# nixie_tubes.net
KiCad netlist of a schematic drawn in EAGLE
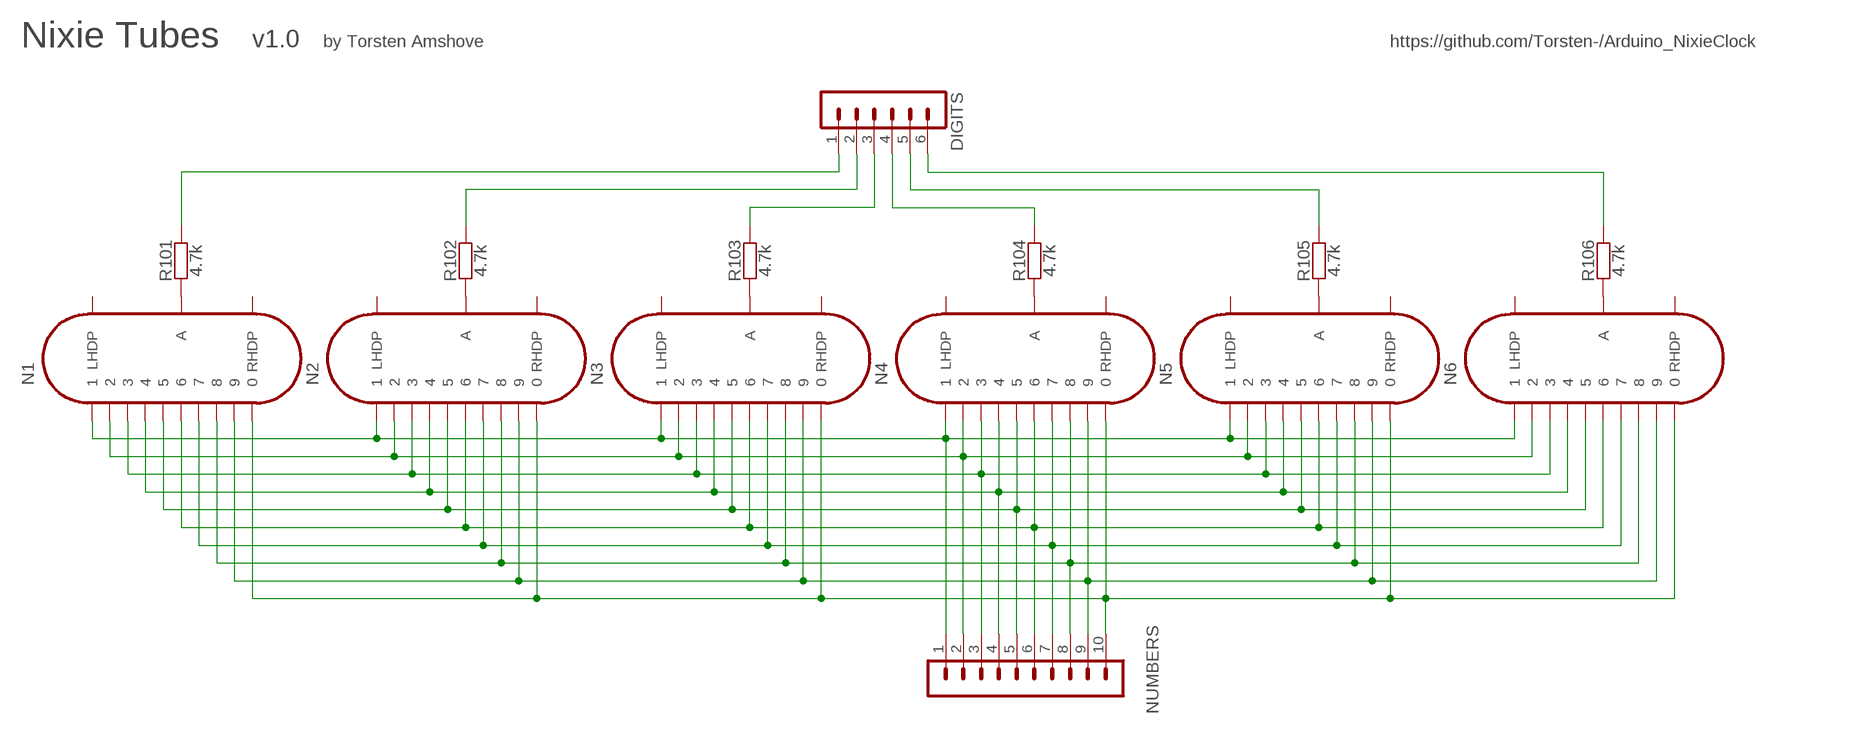
[diagram p0: schematic, sheet 1]

(export (version "E")
  (design (tool "Eeschema 10.0.6"))
  (components
    (comp (ref "DIGITS")
      (value "MA06-1")
      (footprint "eagle-import:MA06-1")
      (libsource (lib "eagle-import") (part "MA06-1"))
    )
    (comp (ref "N1")
      (value "IN-14")
      (footprint "eagle-import:IN-14")
      (libsource (lib "eagle-import") (part "IN-14"))
    )
    (comp (ref "N2")
      (value "IN-14")
      (footprint "eagle-import:IN-14")
      (libsource (lib "eagle-import") (part "IN-14"))
    )
    (comp (ref "N3")
      (value "IN-14")
      (footprint "eagle-import:IN-14")
      (libsource (lib "eagle-import") (part "IN-14"))
    )
    (comp (ref "N4")
      (value "IN-14")
      (footprint "eagle-import:IN-14")
      (libsource (lib "eagle-import") (part "IN-14"))
    )
    (comp (ref "N5")
      (value "IN-14")
      (footprint "eagle-import:IN-14")
      (libsource (lib "eagle-import") (part "IN-14"))
    )
    (comp (ref "N6")
      (value "IN-14")
      (footprint "eagle-import:IN-14")
      (libsource (lib "eagle-import") (part "IN-14"))
    )
    (comp (ref "NUMBERS")
      (value "MA10-1")
      (footprint "eagle-import:MA10-1")
      (libsource (lib "eagle-import") (part "MA10-1"))
    )
    (comp (ref "R101")
      (value "4.7k")
      (footprint "eagle-import:R0207_10")
      (libsource (lib "eagle-import") (part "RESISTOR-10"))
    )
    (comp (ref "R102")
      (value "4.7k")
      (footprint "eagle-import:R0207_10")
      (libsource (lib "eagle-import") (part "RESISTOR-10"))
    )
    (comp (ref "R103")
      (value "4.7k")
      (footprint "eagle-import:R0207_10")
      (libsource (lib "eagle-import") (part "RESISTOR-10"))
    )
    (comp (ref "R104")
      (value "4.7k")
      (footprint "eagle-import:R0207_10")
      (libsource (lib "eagle-import") (part "RESISTOR-10"))
    )
    (comp (ref "R105")
      (value "4.7k")
      (footprint "eagle-import:R0207_10")
      (libsource (lib "eagle-import") (part "RESISTOR-10"))
    )
    (comp (ref "R106")
      (value "4.7k")
      (footprint "eagle-import:R0207_10")
      (libsource (lib "eagle-import") (part "RESISTOR-10"))
    )
  )
  (nets
    (net (code "1") (name "Net-(DIGITS-Pad1)") (class "Default")
      (node (ref "DIGITS") (pin "1") (pinfunction "1_1") (pintype "passive"))
      (node (ref "R101") (pin "2") (pinfunction "2_2") (pintype "passive"))
    )
    (net (code "2") (name "Net-(DIGITS-Pad2)") (class "Default")
      (node (ref "DIGITS") (pin "2") (pinfunction "2_2") (pintype "passive"))
      (node (ref "R102") (pin "2") (pinfunction "2_2") (pintype "passive"))
    )
    (net (code "3") (name "Net-(DIGITS-Pad3)") (class "Default")
      (node (ref "DIGITS") (pin "3") (pinfunction "3_3") (pintype "passive"))
      (node (ref "R103") (pin "2") (pinfunction "2_2") (pintype "passive"))
    )
    (net (code "4") (name "Net-(DIGITS-Pad4)") (class "Default")
      (node (ref "DIGITS") (pin "4") (pinfunction "4_4") (pintype "passive"))
      (node (ref "R104") (pin "2") (pinfunction "2_2") (pintype "passive"))
    )
    (net (code "5") (name "Net-(DIGITS-Pad5)") (class "Default")
      (node (ref "DIGITS") (pin "5") (pinfunction "5_5") (pintype "passive"))
      (node (ref "R105") (pin "2") (pinfunction "2_2") (pintype "passive"))
    )
    (net (code "6") (name "Net-(DIGITS-Pad6)") (class "Default")
      (node (ref "DIGITS") (pin "6") (pinfunction "6_6") (pintype "passive"))
      (node (ref "R106") (pin "2") (pinfunction "2_2") (pintype "passive"))
    )
    (net (code "7") (name "Net-(N1-Pad0)") (class "Default")
      (node (ref "N1") (pin "0") (pinfunction "0_0") (pintype "bidirectional"))
      (node (ref "N2") (pin "0") (pinfunction "0_0") (pintype "bidirectional"))
      (node (ref "N3") (pin "0") (pinfunction "0_0") (pintype "bidirectional"))
      (node (ref "N4") (pin "0") (pinfunction "0_0") (pintype "bidirectional"))
      (node (ref "N5") (pin "0") (pinfunction "0_0") (pintype "bidirectional"))
      (node (ref "N6") (pin "0") (pinfunction "0_0") (pintype "bidirectional"))
      (node (ref "NUMBERS") (pin "10") (pinfunction "10_10") (pintype "passive"))
    )
    (net (code "8") (name "Net-(N1-Pad1)") (class "Default")
      (node (ref "N1") (pin "1") (pinfunction "1_1") (pintype "bidirectional"))
      (node (ref "N2") (pin "1") (pinfunction "1_1") (pintype "bidirectional"))
      (node (ref "N3") (pin "1") (pinfunction "1_1") (pintype "bidirectional"))
      (node (ref "N4") (pin "1") (pinfunction "1_1") (pintype "bidirectional"))
      (node (ref "N5") (pin "1") (pinfunction "1_1") (pintype "bidirectional"))
      (node (ref "N6") (pin "1") (pinfunction "1_1") (pintype "bidirectional"))
      (node (ref "NUMBERS") (pin "1") (pinfunction "1_1") (pintype "passive"))
    )
    (net (code "9") (name "Net-(N1-Pad2)") (class "Default")
      (node (ref "N1") (pin "2") (pinfunction "2_2") (pintype "bidirectional"))
      (node (ref "N2") (pin "2") (pinfunction "2_2") (pintype "bidirectional"))
      (node (ref "N3") (pin "2") (pinfunction "2_2") (pintype "bidirectional"))
      (node (ref "N4") (pin "2") (pinfunction "2_2") (pintype "bidirectional"))
      (node (ref "N5") (pin "2") (pinfunction "2_2") (pintype "bidirectional"))
      (node (ref "N6") (pin "2") (pinfunction "2_2") (pintype "bidirectional"))
      (node (ref "NUMBERS") (pin "2") (pinfunction "2_2") (pintype "passive"))
    )
    (net (code "10") (name "Net-(N1-Pad3)") (class "Default")
      (node (ref "N1") (pin "3") (pinfunction "3_3") (pintype "bidirectional"))
      (node (ref "N2") (pin "3") (pinfunction "3_3") (pintype "bidirectional"))
      (node (ref "N3") (pin "3") (pinfunction "3_3") (pintype "bidirectional"))
      (node (ref "N4") (pin "3") (pinfunction "3_3") (pintype "bidirectional"))
      (node (ref "N5") (pin "3") (pinfunction "3_3") (pintype "bidirectional"))
      (node (ref "N6") (pin "3") (pinfunction "3_3") (pintype "bidirectional"))
      (node (ref "NUMBERS") (pin "3") (pinfunction "3_3") (pintype "passive"))
    )
    (net (code "11") (name "Net-(N1-Pad4)") (class "Default")
      (node (ref "N1") (pin "4") (pinfunction "4_4") (pintype "bidirectional"))
      (node (ref "N2") (pin "4") (pinfunction "4_4") (pintype "bidirectional"))
      (node (ref "N3") (pin "4") (pinfunction "4_4") (pintype "bidirectional"))
      (node (ref "N4") (pin "4") (pinfunction "4_4") (pintype "bidirectional"))
      (node (ref "N5") (pin "4") (pinfunction "4_4") (pintype "bidirectional"))
      (node (ref "N6") (pin "4") (pinfunction "4_4") (pintype "bidirectional"))
      (node (ref "NUMBERS") (pin "4") (pinfunction "4_4") (pintype "passive"))
    )
    (net (code "12") (name "Net-(N1-Pad5)") (class "Default")
      (node (ref "N1") (pin "5") (pinfunction "5_5") (pintype "bidirectional"))
      (node (ref "N2") (pin "5") (pinfunction "5_5") (pintype "bidirectional"))
      (node (ref "N3") (pin "5") (pinfunction "5_5") (pintype "bidirectional"))
      (node (ref "N4") (pin "5") (pinfunction "5_5") (pintype "bidirectional"))
      (node (ref "N5") (pin "5") (pinfunction "5_5") (pintype "bidirectional"))
      (node (ref "N6") (pin "5") (pinfunction "5_5") (pintype "bidirectional"))
      (node (ref "NUMBERS") (pin "5") (pinfunction "5_5") (pintype "passive"))
    )
    (net (code "13") (name "Net-(N1-Pad6)") (class "Default")
      (node (ref "N1") (pin "6") (pinfunction "6_6") (pintype "bidirectional"))
      (node (ref "N2") (pin "6") (pinfunction "6_6") (pintype "bidirectional"))
      (node (ref "N3") (pin "6") (pinfunction "6_6") (pintype "bidirectional"))
      (node (ref "N4") (pin "6") (pinfunction "6_6") (pintype "bidirectional"))
      (node (ref "N5") (pin "6") (pinfunction "6_6") (pintype "bidirectional"))
      (node (ref "N6") (pin "6") (pinfunction "6_6") (pintype "bidirectional"))
      (node (ref "NUMBERS") (pin "6") (pinfunction "6_6") (pintype "passive"))
    )
    (net (code "14") (name "Net-(N1-Pad7)") (class "Default")
      (node (ref "N1") (pin "7") (pinfunction "7_7") (pintype "bidirectional"))
      (node (ref "N2") (pin "7") (pinfunction "7_7") (pintype "bidirectional"))
      (node (ref "N3") (pin "7") (pinfunction "7_7") (pintype "bidirectional"))
      (node (ref "N4") (pin "7") (pinfunction "7_7") (pintype "bidirectional"))
      (node (ref "N5") (pin "7") (pinfunction "7_7") (pintype "bidirectional"))
      (node (ref "N6") (pin "7") (pinfunction "7_7") (pintype "bidirectional"))
      (node (ref "NUMBERS") (pin "7") (pinfunction "7_7") (pintype "passive"))
    )
    (net (code "15") (name "Net-(N1-Pad8)") (class "Default")
      (node (ref "N1") (pin "8") (pinfunction "8_8") (pintype "bidirectional"))
      (node (ref "N2") (pin "8") (pinfunction "8_8") (pintype "bidirectional"))
      (node (ref "N3") (pin "8") (pinfunction "8_8") (pintype "bidirectional"))
      (node (ref "N4") (pin "8") (pinfunction "8_8") (pintype "bidirectional"))
      (node (ref "N5") (pin "8") (pinfunction "8_8") (pintype "bidirectional"))
      (node (ref "N6") (pin "8") (pinfunction "8_8") (pintype "bidirectional"))
      (node (ref "NUMBERS") (pin "8") (pinfunction "8_8") (pintype "passive"))
    )
    (net (code "16") (name "Net-(N1-Pad9)") (class "Default")
      (node (ref "N1") (pin "9") (pinfunction "9_9") (pintype "bidirectional"))
      (node (ref "N2") (pin "9") (pinfunction "9_9") (pintype "bidirectional"))
      (node (ref "N3") (pin "9") (pinfunction "9_9") (pintype "bidirectional"))
      (node (ref "N4") (pin "9") (pinfunction "9_9") (pintype "bidirectional"))
      (node (ref "N5") (pin "9") (pinfunction "9_9") (pintype "bidirectional"))
      (node (ref "N6") (pin "9") (pinfunction "9_9") (pintype "bidirectional"))
      (node (ref "NUMBERS") (pin "9") (pinfunction "9_9") (pintype "passive"))
    )
    (net (code "17") (name "Net-(N1-PadA)") (class "Default")
      (node (ref "N1") (pin "A") (pinfunction "A_A") (pintype "bidirectional"))
      (node (ref "R101") (pin "1") (pinfunction "1_1") (pintype "passive"))
    )
    (net (code "18") (name "Net-(N2-PadA)") (class "Default")
      (node (ref "N2") (pin "A") (pinfunction "A_A") (pintype "bidirectional"))
      (node (ref "R102") (pin "1") (pinfunction "1_1") (pintype "passive"))
    )
    (net (code "19") (name "Net-(N3-PadA)") (class "Default")
      (node (ref "N3") (pin "A") (pinfunction "A_A") (pintype "bidirectional"))
      (node (ref "R103") (pin "1") (pinfunction "1_1") (pintype "passive"))
    )
    (net (code "20") (name "Net-(N4-PadA)") (class "Default")
      (node (ref "N4") (pin "A") (pinfunction "A_A") (pintype "bidirectional"))
      (node (ref "R104") (pin "1") (pinfunction "1_1") (pintype "passive"))
    )
    (net (code "21") (name "Net-(N5-PadA)") (class "Default")
      (node (ref "N5") (pin "A") (pinfunction "A_A") (pintype "bidirectional"))
      (node (ref "R105") (pin "1") (pinfunction "1_1") (pintype "passive"))
    )
    (net (code "22") (name "Net-(N6-PadA)") (class "Default")
      (node (ref "N6") (pin "A") (pinfunction "A_A") (pintype "bidirectional"))
      (node (ref "R106") (pin "1") (pinfunction "1_1") (pintype "passive"))
    )
    (net (code "23") (name "unconnected-(N1-PadLHDP)") (class "Default")
      (node (ref "N1") (pin "LHDP") (pinfunction "LHDP_LHDP") (pintype "bidirectional"))
    )
    (net (code "24") (name "unconnected-(N1-PadRHDP)") (class "Default")
      (node (ref "N1") (pin "RHDP") (pinfunction "RHDP_RHDP") (pintype "bidirectional"))
    )
    (net (code "25") (name "unconnected-(N2-PadLHDP)") (class "Default")
      (node (ref "N2") (pin "LHDP") (pinfunction "LHDP_LHDP") (pintype "bidirectional"))
    )
    (net (code "26") (name "unconnected-(N2-PadRHDP)") (class "Default")
      (node (ref "N2") (pin "RHDP") (pinfunction "RHDP_RHDP") (pintype "bidirectional"))
    )
    (net (code "27") (name "unconnected-(N3-PadLHDP)") (class "Default")
      (node (ref "N3") (pin "LHDP") (pinfunction "LHDP_LHDP") (pintype "bidirectional"))
    )
    (net (code "28") (name "unconnected-(N3-PadRHDP)") (class "Default")
      (node (ref "N3") (pin "RHDP") (pinfunction "RHDP_RHDP") (pintype "bidirectional"))
    )
    (net (code "29") (name "unconnected-(N4-PadLHDP)") (class "Default")
      (node (ref "N4") (pin "LHDP") (pinfunction "LHDP_LHDP") (pintype "bidirectional"))
    )
    (net (code "30") (name "unconnected-(N4-PadRHDP)") (class "Default")
      (node (ref "N4") (pin "RHDP") (pinfunction "RHDP_RHDP") (pintype "bidirectional"))
    )
    (net (code "31") (name "unconnected-(N5-PadLHDP)") (class "Default")
      (node (ref "N5") (pin "LHDP") (pinfunction "LHDP_LHDP") (pintype "bidirectional"))
    )
    (net (code "32") (name "unconnected-(N5-PadRHDP)") (class "Default")
      (node (ref "N5") (pin "RHDP") (pinfunction "RHDP_RHDP") (pintype "bidirectional"))
    )
    (net (code "33") (name "unconnected-(N6-PadLHDP)") (class "Default")
      (node (ref "N6") (pin "LHDP") (pinfunction "LHDP_LHDP") (pintype "bidirectional"))
    )
    (net (code "34") (name "unconnected-(N6-PadRHDP)") (class "Default")
      (node (ref "N6") (pin "RHDP") (pinfunction "RHDP_RHDP") (pintype "bidirectional"))
    )
  )
)
